# LDO.net
KiCad netlist of a schematic drawn in Altium Designer
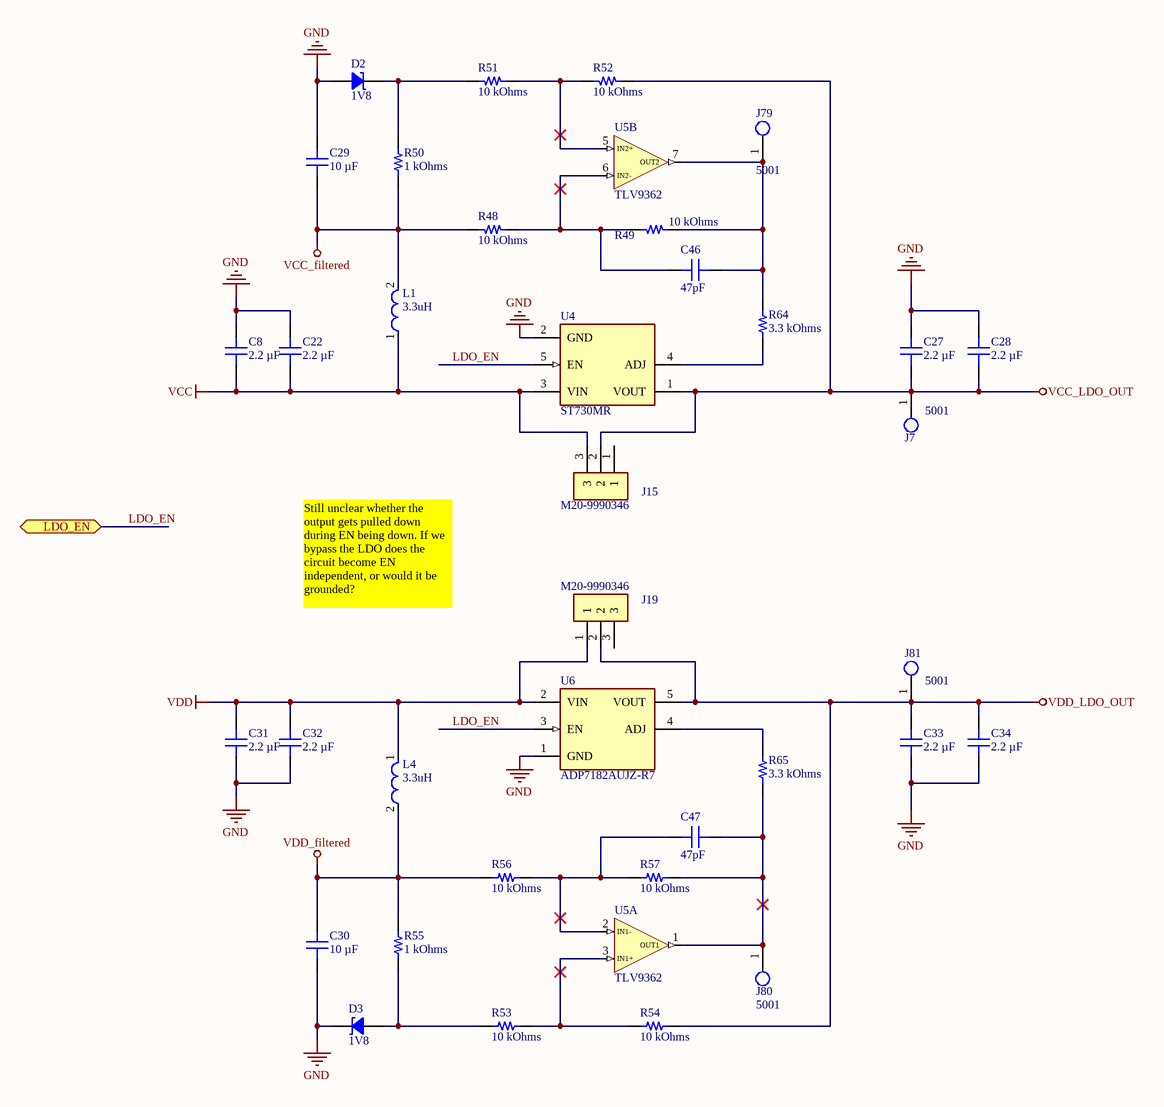
[diagram p0: LDO.SchDoc]

(export (version "E")
  (design (tool "Eeschema 10.0.6"))
  (components
    (comp (ref "C8")
      (value "2.2 µF")
      (footprint "CAP 1206_3216 - 0.8MM")
      (description "CAP CER 2.2UF 25V X7R 1206")
      (fields
        (field (name "PART NUMBER") "885382208001")
        (field (name "CAPACITANCE") "2.2 µF")
        (field (name "MANUFACTURER") "Würth Elektronik")
      )
      (libsource (lib "Celestial Altium Library - altium_library") (part "Capacitor"))
    )
    (comp (ref "C22")
      (value "2.2 µF")
      (footprint "CAP 1206_3216 - 0.8MM")
      (description "CAP CER 2.2UF 25V X7R 1206")
      (fields
        (field (name "PART NUMBER") "885382208001")
        (field (name "CAPACITANCE") "2.2 µF")
        (field (name "MANUFACTURER") "Würth Elektronik")
      )
      (libsource (lib "Celestial Altium Library - altium_library") (part "Capacitor"))
    )
    (comp (ref "C27")
      (value "2.2 µF")
      (footprint "CAP 1206_3216 - 0.8MM")
      (description "CAP CER 2.2UF 25V X7R 1206")
      (fields
        (field (name "PART NUMBER") "885382208001")
        (field (name "CAPACITANCE") "2.2 µF")
        (field (name "MANUFACTURER") "Würth Elektronik")
      )
      (libsource (lib "Celestial Altium Library - altium_library") (part "Capacitor"))
    )
    (comp (ref "C28")
      (value "2.2 µF")
      (footprint "CAP 1206_3216 - 0.8MM")
      (description "CAP CER 2.2UF 25V X7R 1206")
      (fields
        (field (name "PART NUMBER") "885382208001")
        (field (name "CAPACITANCE") "2.2 µF")
        (field (name "MANUFACTURER") "Würth Elektronik")
      )
      (libsource (lib "Celestial Altium Library - altium_library") (part "Capacitor"))
    )
    (comp (ref "C29")
      (value "10 µF")
      (footprint "CAP 1206_3216 - 0.8MM")
      (description "CAP CER 10UF 25V X7R 1206")
      (fields
        (field (name "PART NUMBER") "885012208069")
        (field (name "CAPACITANCE") "10 µF")
        (field (name "MANUFACTURER") "Würth Elektronik")
      )
      (libsource (lib "Celestial Altium Library - altium_library") (part "Capacitor"))
    )
    (comp (ref "C30")
      (value "10 µF")
      (footprint "CAP 1206_3216 - 0.8MM")
      (description "CAP CER 10UF 25V X7R 1206")
      (fields
        (field (name "PART NUMBER") "885012208069")
        (field (name "CAPACITANCE") "10 µF")
        (field (name "MANUFACTURER") "Würth Elektronik")
      )
      (libsource (lib "Celestial Altium Library - altium_library") (part "Capacitor"))
    )
    (comp (ref "C31")
      (value "2.2 µF")
      (footprint "CAP 1206_3216 - 0.8MM")
      (description "CAP CER 2.2UF 25V X7R 1206")
      (fields
        (field (name "PART NUMBER") "885382208001")
        (field (name "CAPACITANCE") "2.2 µF")
        (field (name "MANUFACTURER") "Würth Elektronik")
      )
      (libsource (lib "Celestial Altium Library - altium_library") (part "Capacitor"))
    )
    (comp (ref "C32")
      (value "2.2 µF")
      (footprint "CAP 1206_3216 - 0.8MM")
      (description "CAP CER 2.2UF 25V X7R 1206")
      (fields
        (field (name "PART NUMBER") "885382208001")
        (field (name "CAPACITANCE") "2.2 µF")
        (field (name "MANUFACTURER") "Würth Elektronik")
      )
      (libsource (lib "Celestial Altium Library - altium_library") (part "Capacitor"))
    )
    (comp (ref "C33")
      (value "2.2 µF")
      (footprint "CAP 1206_3216 - 0.8MM")
      (description "CAP CER 2.2UF 25V X7R 1206")
      (fields
        (field (name "PART NUMBER") "885382208001")
        (field (name "CAPACITANCE") "2.2 µF")
        (field (name "MANUFACTURER") "Würth Elektronik")
      )
      (libsource (lib "Celestial Altium Library - altium_library") (part "Capacitor"))
    )
    (comp (ref "C34")
      (value "2.2 µF")
      (footprint "CAP 1206_3216 - 0.8MM")
      (description "CAP CER 2.2UF 25V X7R 1206")
      (fields
        (field (name "PART NUMBER") "885382208001")
        (field (name "CAPACITANCE") "2.2 µF")
        (field (name "MANUFACTURER") "Würth Elektronik")
      )
      (libsource (lib "Celestial Altium Library - altium_library") (part "Capacitor"))
    )
    (comp (ref "C46")
      (value "47pF")
      (footprint "CAP 1206_3216 - 1.8MM")
      (description "CAP CER 47PF 1KV C0G/NP0 1206")
      (fields
        (field (name "PART NUMBER") "1206AA470KAT1A")
        (field (name "CAPACITANCE") "47pF")
        (field (name "MANUFACTURER") "AVX Corporation")
      )
      (libsource (lib "Celestial Altium Library - altium_library") (part "Capacitor"))
    )
    (comp (ref "C47")
      (value "47pF")
      (footprint "CAP 1206_3216 - 1.8MM")
      (description "CAP CER 47PF 1KV C0G/NP0 1206")
      (fields
        (field (name "PART NUMBER") "1206AA470KAT1A")
        (field (name "CAPACITANCE") "47pF")
        (field (name "MANUFACTURER") "AVX Corporation")
      )
      (libsource (lib "Celestial Altium Library - altium_library") (part "Capacitor"))
    )
    (comp (ref "D2") (value "1V8") (footprint "SOD323") (libsource (lib "za_koncar") (part "BZX38450-C1V8X")))
    (comp (ref "D3") (value "1V8") (footprint "SOD323") (libsource (lib "za_koncar") (part "BZX38450-C1V8X")))
    (comp (ref "J7")
      (value "5001")
      (footprint "FP-5001-MFG")
      (description "PC TEST POINT MINIATURE BLACK")
      (libsource (lib "za_koncar") (part "CMP-2000-05181-2"))
    )
    (comp (ref "J15")
      (value "M20-9990346")
      (footprint "HDRV3W64P0X254_1X3_762X254X864P")
      (description "Connector")
      (fields (field (name "MOUSER PART NUMBER") "855-M20-9990346"))
      (libsource (lib "") (part "M20-9990346_1"))
    )
    (comp (ref "J19")
      (value "M20-9990346")
      (footprint "HDRV3W64P0X254_1X3_762X254X864P")
      (description "Connector")
      (fields (field (name "MOUSER PART NUMBER") "855-M20-9990346"))
      (libsource (lib "za_koncar") (part "M20-9990346"))
    )
    (comp (ref "J79")
      (value "5001")
      (footprint "FP-5001-MFG")
      (description "PC TEST POINT MINIATURE BLACK")
      (libsource (lib "za_koncar") (part "CMP-2000-05181-2"))
    )
    (comp (ref "J80")
      (value "5001")
      (footprint "FP-5001-MFG")
      (description "PC TEST POINT MINIATURE BLACK")
      (libsource (lib "za_koncar") (part "CMP-2000-05181-2"))
    )
    (comp (ref "J81")
      (value "5001")
      (footprint "FP-5001-MFG")
      (description "PC TEST POINT MINIATURE BLACK")
      (libsource (lib "za_koncar") (part "CMP-2000-05181-2"))
    )
    (comp (ref "L1")
      (value "3.3uH")
      (footprint "FP-MLZ2012-1_25-IPC_B")
      (description "Shielded Multilayer Inductor 3.3uH ±20% 500mA 260mΩ SMD 0805")
      (fields (field (name "TOLERANCE") "20%"))
      (libsource (lib "za_koncar") (part "MLZ2012M"))
    )
    (comp (ref "L4")
      (value "3.3uH")
      (footprint "FP-MLZ2012-1_25-IPC_B")
      (description "Shielded Multilayer Inductor 3.3uH ±20% 500mA 260mΩ SMD 0805")
      (fields (field (name "TOLERANCE") "20%"))
      (libsource (lib "") (part "MLZ2012M_1"))
    )
    (comp (ref "R48")
      (value "10 kOhms")
      (footprint "YAGEO RES 1206_3216")
      (description "RES SMD 10K OHM 1% 1/4W 1206")
      (fields (field (name "PART NUMBER") "RT1206FRE0710KL") (field (name "MANUFACTURER") "Yageo"))
      (libsource (lib "Celestial Altium Library - altium_library") (part "Resistor"))
    )
    (comp (ref "R49")
      (value "10 kOhms")
      (footprint "YAGEO RES 1206_3216")
      (description "RES SMD 10K OHM 1% 1/4W 1206")
      (fields (field (name "PART NUMBER") "RT1206FRE0710KL") (field (name "MANUFACTURER") "Yageo"))
      (libsource (lib "Celestial Altium Library - altium_library") (part "Resistor"))
    )
    (comp (ref "R50")
      (value "1 kOhms")
      (footprint "YAGEO RES 1206_3216")
      (description "RES SMD 1K OHM 1% 1/4W 1206")
      (fields (field (name "PART NUMBER") "RT1206FRE071KL") (field (name "MANUFACTURER") "Yageo"))
      (libsource (lib "Celestial Altium Library - altium_library") (part "Resistor"))
    )
    (comp (ref "R51")
      (value "10 kOhms")
      (footprint "YAGEO RES 1206_3216")
      (description "RES SMD 10K OHM 1% 1/4W 1206")
      (fields (field (name "PART NUMBER") "RT1206FRE0710KL") (field (name "MANUFACTURER") "Yageo"))
      (libsource (lib "Celestial Altium Library - altium_library") (part "Resistor"))
    )
    (comp (ref "R52")
      (value "10 kOhms")
      (footprint "YAGEO RES 1206_3216")
      (description "RES SMD 10K OHM 1% 1/4W 1206")
      (fields (field (name "PART NUMBER") "RT1206FRE0710KL") (field (name "MANUFACTURER") "Yageo"))
      (libsource (lib "Celestial Altium Library - altium_library") (part "Resistor"))
    )
    (comp (ref "R53")
      (value "10 kOhms")
      (footprint "YAGEO RES 1206_3216")
      (description "RES SMD 10K OHM 1% 1/4W 1206")
      (fields (field (name "PART NUMBER") "RT1206FRE0710KL") (field (name "MANUFACTURER") "Yageo"))
      (libsource (lib "Celestial Altium Library - altium_library") (part "Resistor"))
    )
    (comp (ref "R54")
      (value "10 kOhms")
      (footprint "YAGEO RES 1206_3216")
      (description "RES SMD 10K OHM 1% 1/4W 1206")
      (fields (field (name "PART NUMBER") "RT1206FRE0710KL") (field (name "MANUFACTURER") "Yageo"))
      (libsource (lib "Celestial Altium Library - altium_library") (part "Resistor"))
    )
    (comp (ref "R55")
      (value "1 kOhms")
      (footprint "YAGEO RES 1206_3216")
      (description "RES SMD 1K OHM 1% 1/4W 1206")
      (fields (field (name "PART NUMBER") "RT1206FRE071KL") (field (name "MANUFACTURER") "Yageo"))
      (libsource (lib "Celestial Altium Library - altium_library") (part "Resistor"))
    )
    (comp (ref "R56")
      (value "10 kOhms")
      (footprint "YAGEO RES 1206_3216")
      (description "RES SMD 10K OHM 1% 1/4W 1206")
      (fields (field (name "PART NUMBER") "RT1206FRE0710KL") (field (name "MANUFACTURER") "Yageo"))
      (libsource (lib "Celestial Altium Library - altium_library") (part "Resistor"))
    )
    (comp (ref "R57")
      (value "10 kOhms")
      (footprint "YAGEO RES 1206_3216")
      (description "RES SMD 10K OHM 1% 1/4W 1206")
      (fields (field (name "PART NUMBER") "RT1206FRE0710KL") (field (name "MANUFACTURER") "Yageo"))
      (libsource (lib "Celestial Altium Library - altium_library") (part "Resistor"))
    )
    (comp (ref "R64")
      (value "3.3 kOhms")
      (footprint "YAGEO RES 1206_3216")
      (description "RES SMD 3.3K OHM 1% 1/4W 1206")
      (fields (field (name "PART NUMBER") "RT1206FRE073K3L") (field (name "MANUFACTURER") "Yageo"))
      (libsource (lib "Celestial Altium Library - altium_library") (part "Resistor"))
    )
    (comp (ref "R65")
      (value "3.3 kOhms")
      (footprint "YAGEO RES 1206_3216")
      (description "RES SMD 3.3K OHM 1% 1/4W 1206")
      (fields (field (name "PART NUMBER") "RT1206FRE073K3L") (field (name "MANUFACTURER") "Yageo"))
      (libsource (lib "Celestial Altium Library - altium_library") (part "Resistor"))
    )
    (comp (ref "U4")
      (value "ST730MR")
      (footprint "FP-UJ-5-IPC_B")
      (libsource (lib "za_koncar") (part "ST730MR"))
    )
    (comp (ref "U5")
      (value "TLV9362")
      (footprint "za_koncar:SOIC8-127P600X175-8N")
      (description "TLV936x 10-MHz, 40-V, RRO, Operational Amplifie")
      (libsource (lib "za_koncar") (part "TLV9362"))
    )
    (comp (ref "U6")
      (value "ADP7182AUJZ-R7")
      (footprint "FP-UJ-5-IPC_B")
      (description "IC REG LIN NEG ADJ 200MA 5TSOT")
      (fields
        (field (name "MANUFACTURER") "Analog Devices")
        (field (name "OCTOPART") "https://octopart.com/adp7182aujz-r7-analog+devices-21054665")
      )
      (libsource (lib "za_koncar") (part "ADP7182"))
    )
  )
  (nets
    (net (code "1") (name "/LDO_EN") (class "Default")
      (node (ref "U4") (pin "5") (pinfunction "EN_5") (pintype "input"))
      (node (ref "U6") (pin "3") (pinfunction "EN_3") (pintype "input"))
    )
    (net (code "2") (name "GND") (class "Default")
      (node (ref "C22") (pin "1") (pinfunction "1_1") (pintype "passive"))
      (node (ref "C27") (pin "1") (pinfunction "1_1") (pintype "passive"))
      (node (ref "C28") (pin "1") (pinfunction "1_1") (pintype "passive"))
      (node (ref "C29") (pin "1") (pinfunction "1_1") (pintype "passive"))
      (node (ref "C30") (pin "1") (pinfunction "1_1") (pintype "passive"))
      (node (ref "C31") (pin "1") (pinfunction "1_1") (pintype "passive"))
      (node (ref "C32") (pin "1") (pinfunction "1_1") (pintype "passive"))
      (node (ref "C33") (pin "1") (pinfunction "1_1") (pintype "passive"))
      (node (ref "C34") (pin "1") (pinfunction "1_1") (pintype "passive"))
      (node (ref "C8") (pin "1") (pinfunction "1_1") (pintype "passive"))
      (node (ref "D2") (pin "1") (pinfunction "1_1") (pintype "passive"))
      (node (ref "D3") (pin "2") (pinfunction "2_2") (pintype "passive"))
      (node (ref "U4") (pin "2") (pinfunction "GND_2") (pintype "power_in"))
      (node (ref "U6") (pin "1") (pinfunction "GND_1") (pintype "power_in"))
    )
    (net (code "3") (name "Net-(D2-Pad2)") (class "Default")
      (node (ref "D2") (pin "2") (pinfunction "2_2") (pintype "passive"))
      (node (ref "R50") (pin "2") (pinfunction "2_2") (pintype "passive"))
      (node (ref "R51") (pin "2") (pinfunction "2_2") (pintype "passive"))
    )
    (net (code "4") (name "Net-(D3-Pad1)") (class "Default")
      (node (ref "D3") (pin "1") (pinfunction "1_1") (pintype "passive"))
      (node (ref "R53") (pin "2") (pinfunction "2_2") (pintype "passive"))
      (node (ref "R55") (pin "1") (pinfunction "1_1") (pintype "passive"))
    )
    (net (code "5") (name "Net-(U4-ADJ)") (class "Default")
      (node (ref "R64") (pin "2") (pinfunction "2_2") (pintype "passive"))
      (node (ref "U4") (pin "4") (pinfunction "ADJ_4") (pintype "passive"))
    )
    (net (code "6") (name "Net-(U5A-IN1+)") (class "Default")
      (node (ref "R53") (pin "1") (pinfunction "1_1") (pintype "passive"))
      (node (ref "R54") (pin "2") (pinfunction "2_2") (pintype "passive"))
      (node (ref "U5") (pin "3") (pinfunction "IN1+_3") (pintype "input"))
    )
    (net (code "7") (name "Net-(U5A-IN1-)") (class "Default")
      (node (ref "C47") (pin "1") (pinfunction "1_1") (pintype "passive"))
      (node (ref "R56") (pin "1") (pinfunction "1_1") (pintype "passive"))
      (node (ref "R57") (pin "2") (pinfunction "2_2") (pintype "passive"))
      (node (ref "U5") (pin "2") (pinfunction "IN1-_2") (pintype "input"))
    )
    (net (code "8") (name "Net-(U5A-OUT1)") (class "Default")
      (node (ref "C47") (pin "2") (pinfunction "2_2") (pintype "passive"))
      (node (ref "J80") (pin "1") (pinfunction "1_1") (pintype "passive"))
      (node (ref "R57") (pin "1") (pinfunction "1_1") (pintype "passive"))
      (node (ref "R65") (pin "2") (pinfunction "2_2") (pintype "passive"))
      (node (ref "U5") (pin "1") (pinfunction "OUT1_1") (pintype "output"))
    )
    (net (code "9") (name "Net-(U5B-IN2+)") (class "Default")
      (node (ref "R51") (pin "1") (pinfunction "1_1") (pintype "passive"))
      (node (ref "R52") (pin "2") (pinfunction "2_2") (pintype "passive"))
      (node (ref "U5") (pin "5") (pinfunction "IN2+_5") (pintype "input"))
    )
    (net (code "10") (name "Net-(U5B-IN2-)") (class "Default")
      (node (ref "C46") (pin "1") (pinfunction "1_1") (pintype "passive"))
      (node (ref "R48") (pin "1") (pinfunction "1_1") (pintype "passive"))
      (node (ref "R49") (pin "2") (pinfunction "2_2") (pintype "passive"))
      (node (ref "U5") (pin "6") (pinfunction "IN2-_6") (pintype "input"))
    )
    (net (code "11") (name "Net-(U5B-OUT2)") (class "Default")
      (node (ref "C46") (pin "2") (pinfunction "2_2") (pintype "passive"))
      (node (ref "J79") (pin "1") (pinfunction "1_1") (pintype "passive"))
      (node (ref "R49") (pin "1") (pinfunction "1_1") (pintype "passive"))
      (node (ref "R64") (pin "1") (pinfunction "1_1") (pintype "passive"))
      (node (ref "U5") (pin "7") (pinfunction "OUT2_7") (pintype "output"))
    )
    (net (code "12") (name "Net-(U6-ADJ)") (class "Default")
      (node (ref "R65") (pin "1") (pinfunction "1_1") (pintype "passive"))
      (node (ref "U6") (pin "4") (pinfunction "ADJ_4") (pintype "passive"))
    )
    (net (code "13") (name "VCC") (class "Default")
      (node (ref "C22") (pin "2") (pinfunction "2_2") (pintype "passive"))
      (node (ref "C8") (pin "2") (pinfunction "2_2") (pintype "passive"))
      (node (ref "J15") (pin "3") (pinfunction "3_3") (pintype "passive"))
      (node (ref "L1") (pin "1") (pinfunction "1_1") (pintype "passive"))
      (node (ref "U4") (pin "3") (pinfunction "VIN_3") (pintype "power_in"))
    )
    (net (code "14") (name "VCC_LDO_OUT") (class "Default")
      (node (ref "C27") (pin "2") (pinfunction "2_2") (pintype "passive"))
      (node (ref "C28") (pin "2") (pinfunction "2_2") (pintype "passive"))
      (node (ref "J15") (pin "2") (pinfunction "2_2") (pintype "passive"))
      (node (ref "J7") (pin "1") (pinfunction "1_1") (pintype "passive"))
      (node (ref "R52") (pin "1") (pinfunction "1_1") (pintype "passive"))
      (node (ref "U4") (pin "1") (pinfunction "VOUT_1") (pintype "power_in"))
    )
    (net (code "15") (name "VCC_filtered") (class "Default")
      (node (ref "C29") (pin "2") (pinfunction "2_2") (pintype "passive"))
      (node (ref "L1") (pin "2") (pinfunction "2_2") (pintype "passive"))
      (node (ref "R48") (pin "2") (pinfunction "2_2") (pintype "passive"))
      (node (ref "R50") (pin "1") (pinfunction "1_1") (pintype "passive"))
    )
    (net (code "16") (name "VDD") (class "Default")
      (node (ref "C31") (pin "2") (pinfunction "2_2") (pintype "passive"))
      (node (ref "C32") (pin "2") (pinfunction "2_2") (pintype "passive"))
      (node (ref "J19") (pin "1") (pinfunction "1_1") (pintype "passive"))
      (node (ref "L4") (pin "1") (pinfunction "1_1") (pintype "passive"))
      (node (ref "U6") (pin "2") (pinfunction "VIN_2") (pintype "power_in"))
    )
    (net (code "17") (name "VDD_LDO_OUT") (class "Default")
      (node (ref "C33") (pin "2") (pinfunction "2_2") (pintype "passive"))
      (node (ref "C34") (pin "2") (pinfunction "2_2") (pintype "passive"))
      (node (ref "J19") (pin "2") (pinfunction "2_2") (pintype "passive"))
      (node (ref "J81") (pin "1") (pinfunction "1_1") (pintype "passive"))
      (node (ref "R54") (pin "1") (pinfunction "1_1") (pintype "passive"))
      (node (ref "U6") (pin "5") (pinfunction "VOUT_5") (pintype "power_in"))
    )
    (net (code "18") (name "VDD_filtered") (class "Default")
      (node (ref "C30") (pin "2") (pinfunction "2_2") (pintype "passive"))
      (node (ref "L4") (pin "2") (pinfunction "2_2") (pintype "passive"))
      (node (ref "R55") (pin "2") (pinfunction "2_2") (pintype "passive"))
      (node (ref "R56") (pin "2") (pinfunction "2_2") (pintype "passive"))
    )
    (net (code "19") (name "unconnected-(J15-Pad1)") (class "Default")
      (node (ref "J15") (pin "1") (pinfunction "1_1") (pintype "passive"))
    )
    (net (code "20") (name "unconnected-(J19-Pad3)") (class "Default")
      (node (ref "J19") (pin "3") (pinfunction "3_3") (pintype "passive"))
    )
  )
)
